# 105358-3SC002-01-A_CPU.net
KiCad netlist of a schematic drawn in Altium Designer
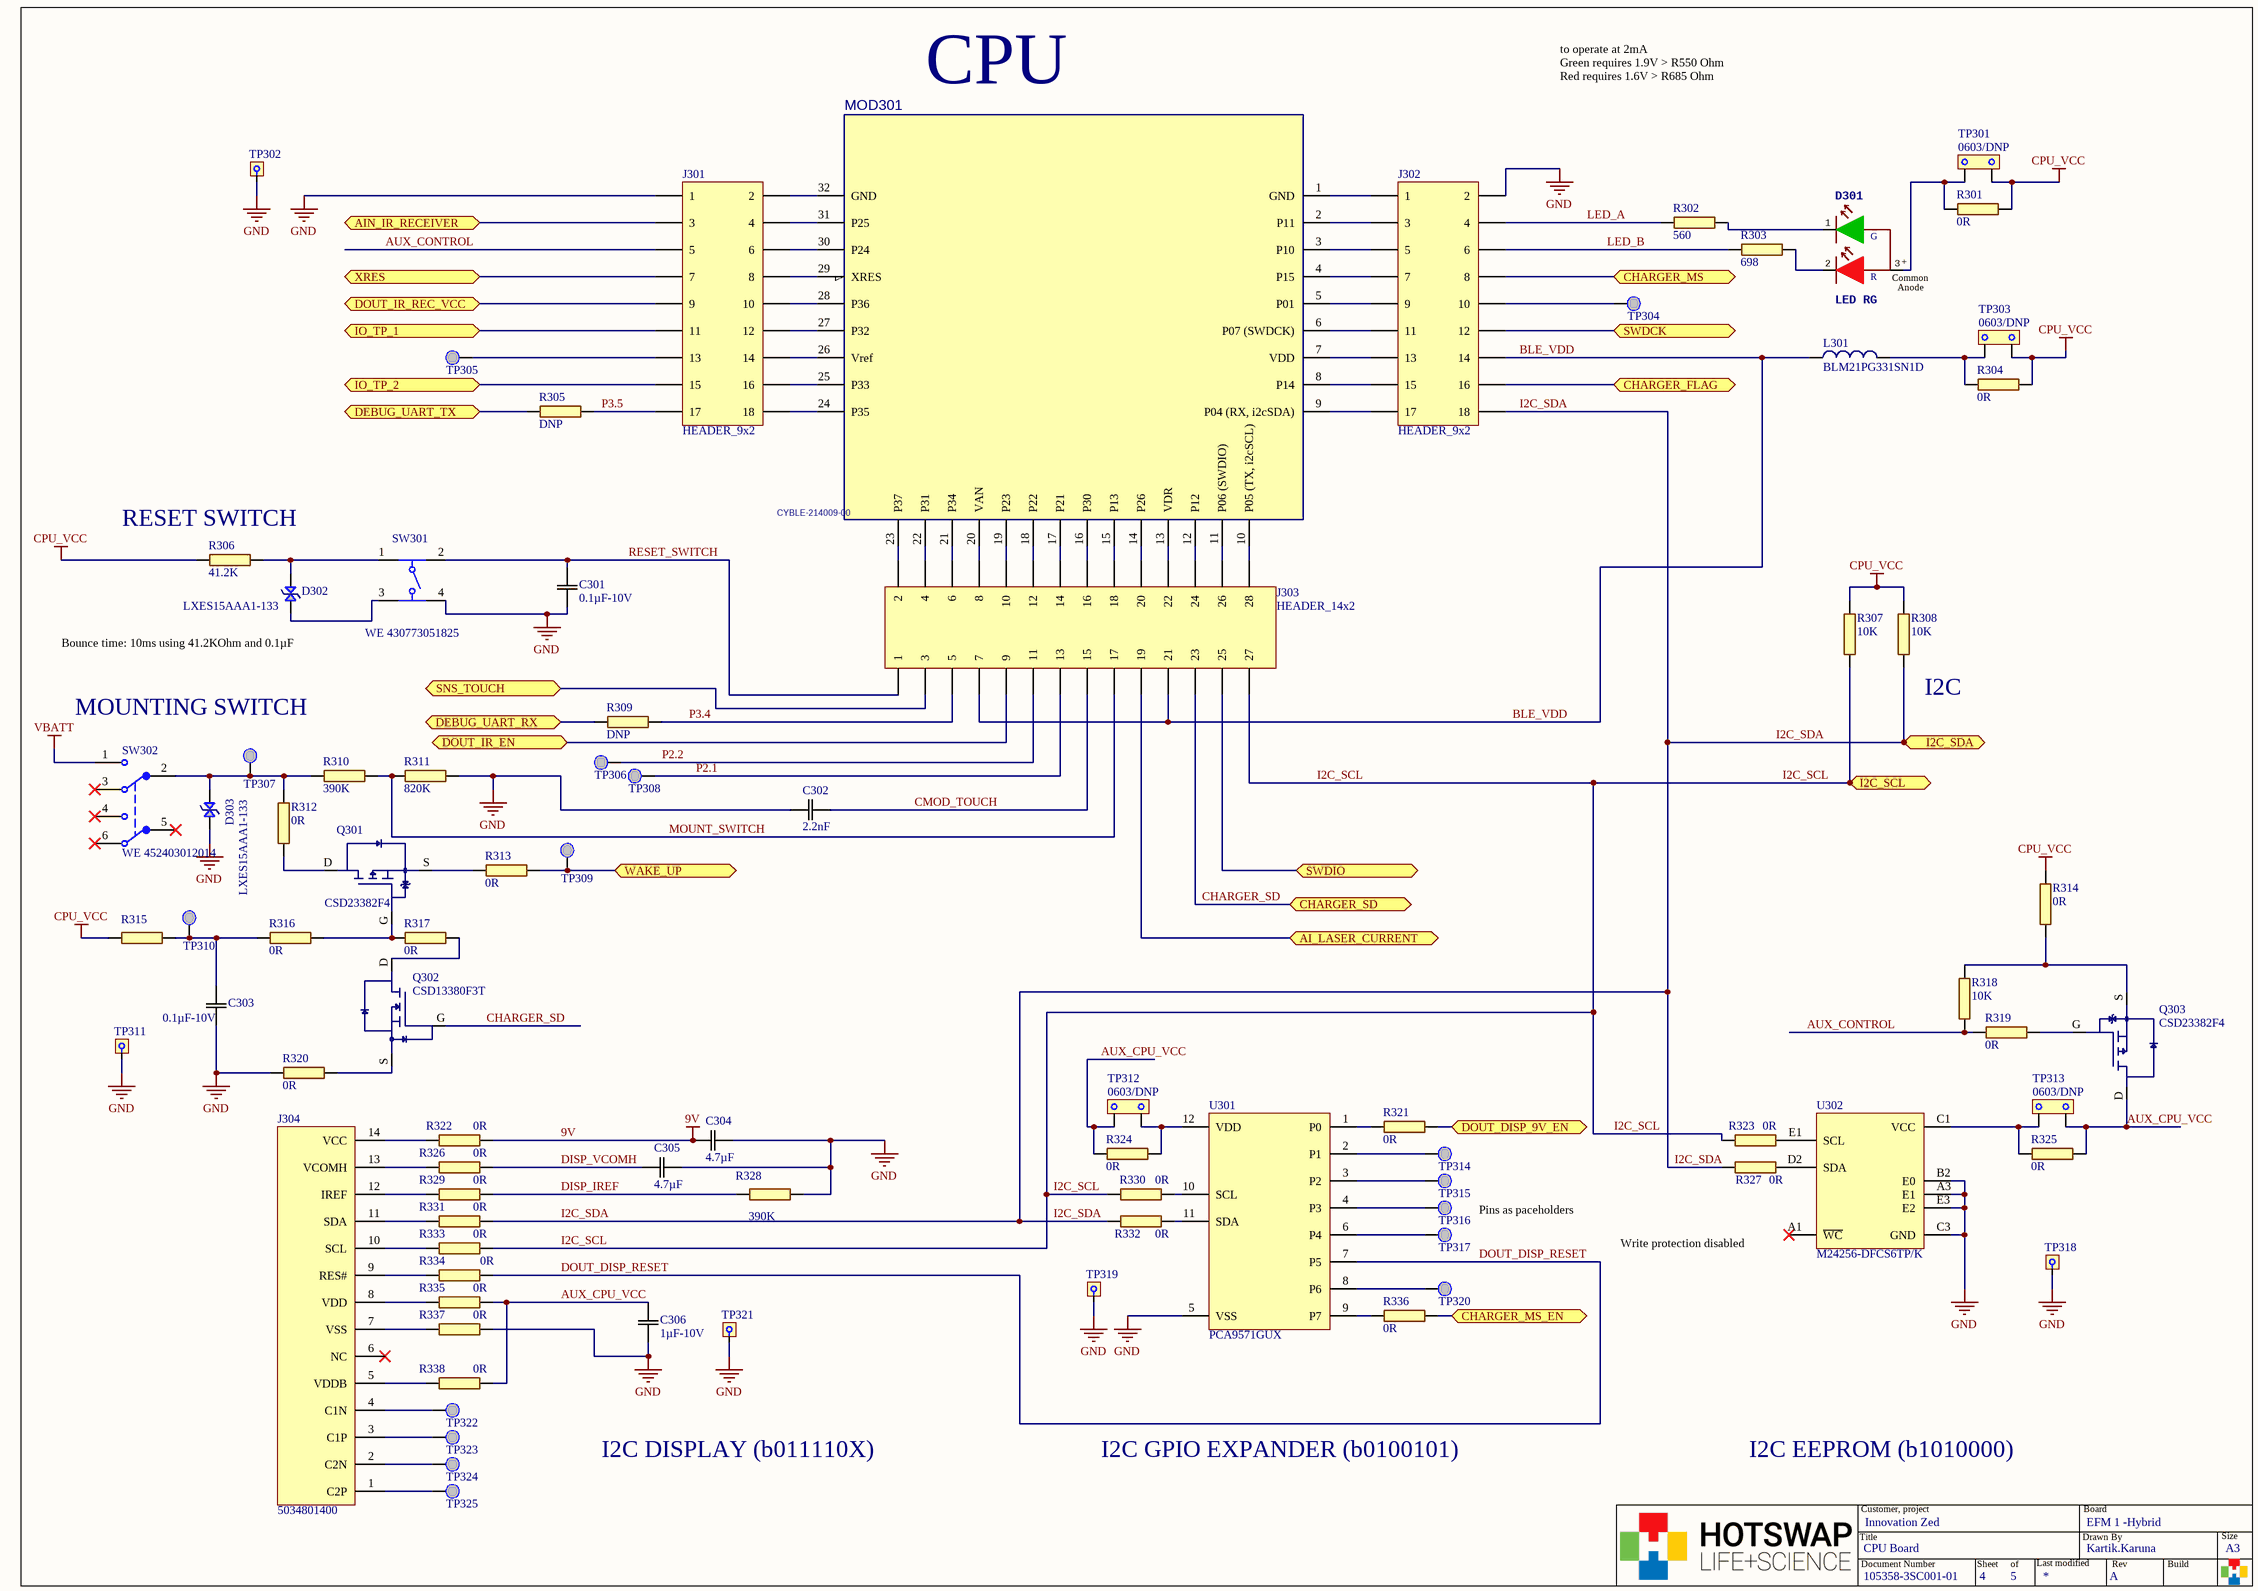
[diagram p0: 105358-3SC002-01-A_CPU.SchDoc]

(export (version "E")
  (design (tool "Eeschema 10.0.6"))
  (components
    (comp (ref "C301")
      (value "0.1µF-10V")
      (footprint "0402C_HIGH_DENSITY")
      (description "0.1µF ±10% 10V X5R Ceramic Capacitor 0402")
      (fields
        (field (name "MANUFACTURER PART NUMBER") "CC0402KRX5R6BB104")
        (field (name "MANUFACTURER") "Yageo")
      )
      (libsource (lib "ConnectMedical") (part "0402C-0.1uF-10V"))
    )
    (comp (ref "C302")
      (value "2.2nF")
      (footprint "0402C_HIGH_DENSITY")
      (description "2.2nF ±10% 50V X5R Ceramic Capacitor 0402")
      (fields
        (field (name "MANUFACTURER PART NUMBER") "GRM155R61H222KA01D")
        (field (name "MANUFACTURER") "Murata Electronics North America")
      )
      (libsource (lib "ConnectMedical") (part "0402C-2.2nF-50V"))
    )
    (comp (ref "C303")
      (value "0.1µF-10V")
      (footprint "0402C_HIGH_DENSITY")
      (description "0.1µF ±10% 10V X5R Ceramic Capacitor 0402")
      (fields
        (field (name "MANUFACTURER PART NUMBER") "CC0402KRX5R6BB104")
        (field (name "MANUFACTURER") "Yageo")
      )
      (libsource (lib "ConnectMedical") (part "0402C-0.1uF-10V"))
    )
    (comp (ref "C304")
      (value "4.7µF")
      (footprint "0402C_HIGH_DENSITY")
      (description "4.7µF ±10% 6.3V X5R Ceramic Capacitor 0402")
      (fields
        (field (name "MANUFACTURER PART NUMBER") "C1005X5R0J475K050BC")
        (field (name "MANUFACTURER") "TDK Corporation")
      )
      (libsource (lib "ConnectMedical") (part "0402C-4.7uF-6.3V"))
    )
    (comp (ref "C305")
      (value "4.7µF")
      (footprint "0402C_HIGH_DENSITY")
      (description "4.7µF ±10% 6.3V X5R Ceramic Capacitor 0402")
      (fields
        (field (name "MANUFACTURER PART NUMBER") "C1005X5R0J475K050BC")
        (field (name "MANUFACTURER") "TDK Corporation")
      )
      (libsource (lib "ConnectMedical") (part "0402C-4.7uF-6.3V"))
    )
    (comp (ref "C306")
      (value "1µF-10V")
      (footprint "0402C_HIGH_DENSITY")
      (description "1µF ±10% 10V X5R Ceramic Capacitor 0402")
      (fields
        (field (name "MANUFACTURER PART NUMBER") "CC0402KRX5R6BB105")
        (field (name "MANUFACTURER") "Yageo")
      )
      (libsource (lib "ConnectMedical") (part "0402C-1uF-10V"))
    )
    (comp (ref "D301")
      (value "LED RG")
      (footprint "LED GRN/RED DIFF 1208 R/A SMD")
      (description "LED GRN/RED DIFF 1208 R/A SMD")
      (fields
        (field (name "MANUFACTURER") "Stanley Electric Co")
        (field (name "MANUFACTURER PART NUMBER") "BRPY1211F-TR")
      )
      (libsource (lib "ConnectMedical") (part "LED GRN/RED DIFF 1208 R/A SMD"))
    )
    (comp (ref "D302")
      (value "LXES15AAA1-133")
      (footprint "0402C-GENERIC")
      (description "TVS DIODE 15VWM 0402")
      (fields
        (field (name "MANUFACTURER") "Murata Electronics North America")
        (field (name "DIGI-KEY PART NUMBER") "490-13209-1-ND")
      )
      (libsource (lib "ConnectMedical") (part "TVS DIODE 15VWM 0402"))
    )
    (comp (ref "D303")
      (value "LXES15AAA1-133")
      (footprint "0402C-GENERIC")
      (description "TVS DIODE 15VWM 0402")
      (fields
        (field (name "MANUFACTURER") "Murata Electronics North America")
        (field (name "DIGI-KEY PART NUMBER") "490-13209-1-ND")
      )
      (libsource (lib "ConnectMedical") (part "TVS DIODE 15VWM 0402"))
    )
    (comp (ref "J301")
      (value "HEADER_9x2")
      (footprint "Pin Header 9 x 2 - 2.54mm")
      (description "18 Positions Header Connector 0.100\" (2.54mm) Through Hole Gold or Gold")
      (fields
        (field (name "MANUFACTURER PART NUMBER") "77313-818-18LF")
        (field (name "MANUFACTURER") "Amphenol FCI")
      )
      (libsource (lib "ConnectMedical") (part "HEADER_9x2"))
    )
    (comp (ref "J302")
      (value "HEADER_9x2")
      (footprint "Pin Header 9 x 2 - 2.54mm")
      (description "18 Positions Header Connector 0.100\" (2.54mm) Through Hole Gold or Gold")
      (fields
        (field (name "MANUFACTURER PART NUMBER") "77313-818-18LF")
        (field (name "MANUFACTURER") "Amphenol FCI")
      )
      (libsource (lib "ConnectMedical") (part "HEADER_9x2"))
    )
    (comp (ref "J303")
      (value "HEADER_14x2")
      (footprint "Pin Header 14 x 2 - 2.54mm")
      (description "CONN HEADER VERT DUAL 28POS 2.54")
      (fields
        (field (name "MANUFACTURER PART NUMBER") "61302821121")
        (field (name "MANUFACTURER") "Wurth Electronics Inc.")
      )
      (libsource (lib "ConnectMedical") (part "HEADER_14x2"))
    )
    (comp (ref "J304")
      (value "5034801400")
      (footprint "5034801400")
      (description "Connector molex to OLED Display")
      (fields (field (name "MANUFACTURER") "Molex, LLC") (field (name "DIGI-KEY PART NUMBER") "WM1442CT-ND"))
      (libsource (lib "ConnectMedical") (part "Molex-5034801400"))
    )
    (comp (ref "L301")
      (value "BLM21PG331SN1D")
      (footprint "0805L_HIGH_DENSITY - Hybrid 0402")
      (description "0805 Ferrite Bead 330Ohm@100MHz")
      (fields
        (field (name "DIGI-KEY PART NUMBER") "490-5988-1-ND")
        (field (name "MANUFACTURER") "Murata Electronics North America")
      )
      (libsource (lib "ConnectMedical") (part "BLM21PG331SN1D"))
    )
    (comp (ref "MOD301")
      (value "CYBLE-214009-00")
      (footprint "CYBLE-014008-00_MinKeepOut")
      (description "BLE PSoC Module 4.1")
      (fields
        (field (name "MANUFACTURER") "Cypress Semiconductor Corp")
        (field (name "DIGI-KEY PART NUMBER") "428-3809-ND")
      )
      (libsource (lib "ConnectMedical") (part "CYBLE-214009-00"))
    )
    (comp (ref "Q301")
      (value "CSD23382F4")
      (footprint "CSD23382F4 -DFN65P100X35-3L")
      (description "MOSFET P-CH 12V 22A 3PICOSTAR")
      (fields
        (field (name "DIGI-KEY PART NUMBER") "296-40003-1-ND")
        (field (name "MANUFACTURER") "Texas Instruments")
      )
      (libsource (lib "ConnectMedical") (part "CSD23382F4"))
    )
    (comp (ref "Q302")
      (value "CSD13380F3T")
      (footprint "CSD13380F3-DFN40P69X35-3L")
      (description "12V N-CHANNEL FEMTOFET MOSFET")
      (fields (field (name "MANUFACTURER") "Texas Instruments"))
      (libsource (lib "ConnectMedical") (part "CSD13380F3T"))
    )
    (comp (ref "Q303")
      (value "CSD23382F4")
      (footprint "CSD23382F4 -DFN65P100X35-3L")
      (description "MOSFET P-CH 12V 22A 3PICOSTAR")
      (fields
        (field (name "DIGI-KEY PART NUMBER") "296-40003-1-ND")
        (field (name "MANUFACTURER") "Texas Instruments")
      )
      (libsource (lib "ConnectMedical") (part "CSD23382F4"))
    )
    (comp (ref "R301")
      (value "0R")
      (footprint "0603R-GENRIC")
      (description "RES SMD 0 OHM 1% 1/10W 0603")
      (fields (field (name "POWER") "0.063W"))
      (libsource (lib "ConnectMedical") (part "0603R-0R -1%-0.063W"))
    )
    (comp (ref "R302")
      (value "560")
      (footprint "0402R-GENERIC")
      (description "RES SMD 560OHM 1% 1/16W 0402")
      (fields
        (field (name "DIGI-KEY PART NUMBER") "1276-3473-1-ND")
        (field (name "MANUFACTURER") "Samsung Electro-Mechanics America, Inc.")
      )
      (libsource (lib "ConnectMedical") (part "0402R-560 OHM-1%-0.063W"))
    )
    (comp (ref "R303")
      (value "698")
      (footprint "0402R-GENERIC")
      (description "RES SMD 698 OHM 1% 1/16W 0402")
      (fields (field (name "DIGI-KEY PART NUMBER") "YAG3215CT-ND") (field (name "MANUFACTURER") "Yageo"))
      (libsource (lib "ConnectMedical") (part "0402R-698 OHM-1%-0.063W"))
    )
    (comp (ref "R304")
      (value "0R")
      (footprint "0603R-GENRIC")
      (description "RES SMD 0 OHM 1% 1/10W 0603")
      (fields (field (name "POWER") "0.063W"))
      (libsource (lib "ConnectMedical") (part "0603R-0R -1%-0.063W"))
    )
    (comp (ref "R305")
      (value "DNP")
      (footprint "0402R-GENERIC")
      (libsource (lib "ConnectMedical") (part "0402R-Do Not Place"))
    )
    (comp (ref "R306")
      (value "41.2K")
      (footprint "0402R-GENERIC")
      (description "RES SMD 41.2kOHM 1% 1/16W 0402")
      (fields (field (name "DIGI-KEY PART NUMBER") "YAG3155CT-ND") (field (name "MANUFACTURER") "Yageo"))
      (libsource (lib "ConnectMedical") (part "0402R-41.2k OHM-1%-0.063W"))
    )
    (comp (ref "R307")
      (value "10K")
      (footprint "0402R-GENERIC")
      (description "RES SMD 10kOHM 1% 1/16W 0402")
      (fields (field (name "DIGI-KEY PART NUMBER") "311-10.0KLRCT-ND") (field (name "MANUFACTURER") "Yageo"))
      (libsource (lib "ConnectMedical") (part "0402R-10k OHM-1%-0.063W"))
    )
    (comp (ref "R308")
      (value "10K")
      (footprint "0402R-GENERIC")
      (description "RES SMD 10kOHM 1% 1/16W 0402")
      (fields (field (name "DIGI-KEY PART NUMBER") "311-10.0KLRCT-ND") (field (name "MANUFACTURER") "Yageo"))
      (libsource (lib "ConnectMedical") (part "0402R-10k OHM-1%-0.063W"))
    )
    (comp (ref "R309")
      (value "DNP")
      (footprint "0402R-GENERIC")
      (libsource (lib "ConnectMedical") (part "0402R-Do Not Place"))
    )
    (comp (ref "R310")
      (value "390K")
      (footprint "0402R-GENERIC")
      (description "RES SMD 390kOHM 1% 1/16W 0402")
      (fields (field (name "DIGI-KEY PART NUMBER") "YAG3143CT-ND") (field (name "MANUFACTURER") "Yageo"))
      (libsource (lib "ConnectMedical") (part "0402R-390k OHM-1%-0.063W"))
    )
    (comp (ref "R311")
      (value "820K")
      (footprint "0402R-GENERIC")
      (description "RES SMD 820kOHM 1% 1/16W 0402")
      (fields (field (name "DIGI-KEY PART NUMBER") "YAG3240CT-ND") (field (name "MANUFACTURER") "Yageo"))
      (libsource (lib "ConnectMedical") (part "0402R-820k OHM-1%-0.063W"))
    )
    (comp (ref "R312")
      (value "0R")
      (footprint "0603R-GENRIC")
      (description "RES SMD 0 OHM 1% 1/10W 0603")
      (fields (field (name "POWER") "0.063W"))
      (libsource (lib "") (part "0603R-0R -1%-0.063W_3"))
    )
    (comp (ref "R313")
      (value "0R")
      (footprint "0603R-GENRIC")
      (description "RES SMD 0 OHM 1% 1/10W 0603")
      (fields (field (name "POWER") "0.063W"))
      (libsource (lib "ConnectMedical") (part "0603R-0R -1%-0.063W"))
    )
    (comp (ref "R314")
      (value "0R")
      (footprint "0603R-GENRIC")
      (description "RES SMD 0 OHM 1% 1/10W 0603")
      (fields (field (name "POWER") "0.063W"))
      (libsource (lib "") (part "0603R-0R -1%-0.063W_2"))
    )
    (comp (ref "R315")
      (value "~")
      (footprint "0402R-GENERIC")
      (description "RES SMD 390kOHM 1% 1/16W 0402")
      (fields (field (name "DIGI-KEY PART NUMBER") "YAG3143CT-ND") (field (name "MANUFACTURER") "Yageo"))
      (libsource (lib "ConnectMedical") (part "0402R-390k OHM-1%-0.063W"))
    )
    (comp (ref "R316")
      (value "0R")
      (footprint "0603R-GENRIC")
      (description "RES SMD 0 OHM 1% 1/10W 0603")
      (fields (field (name "POWER") "0.063W"))
      (libsource (lib "") (part "0603R-0R -1%-0.063W_1"))
    )
    (comp (ref "R317")
      (value "0R")
      (footprint "0603R-GENRIC")
      (description "RES SMD 0 OHM 1% 1/10W 0603")
      (fields (field (name "POWER") "0.063W"))
      (libsource (lib "") (part "0603R-0R -1%-0.063W_1"))
    )
    (comp (ref "R318")
      (value "10K")
      (footprint "0402R-GENERIC")
      (description "RES SMD 10kOHM 1% 1/16W 0402")
      (fields (field (name "DIGI-KEY PART NUMBER") "311-10.0KLRCT-ND") (field (name "MANUFACTURER") "Yageo"))
      (libsource (lib "ConnectMedical") (part "0402R-10k OHM-1%-0.063W"))
    )
    (comp (ref "R319")
      (value "0R")
      (footprint "0603R-GENRIC")
      (description "RES SMD 0 OHM 1% 1/10W 0603")
      (fields (field (name "POWER") "0.063W"))
      (libsource (lib "ConnectMedical") (part "0603R-0R -1%-0.063W"))
    )
    (comp (ref "R320")
      (value "0R")
      (footprint "0603R-GENRIC")
      (description "RES SMD 0 OHM 1% 1/10W 0603")
      (fields (field (name "POWER") "0.063W"))
      (libsource (lib "") (part "0603R-0R -1%-0.063W_1"))
    )
    (comp (ref "R321")
      (value "0R")
      (footprint "0603R-GENRIC")
      (description "RES SMD 0 OHM 1% 1/10W 0603")
      (fields (field (name "POWER") "0.063W"))
      (libsource (lib "ConnectMedical") (part "0603R-0R -1%-0.063W"))
    )
    (comp (ref "R322")
      (value "0R")
      (footprint "0603R-GENRIC")
      (description "RES SMD 0 OHM 1% 1/10W 0603")
      (fields (field (name "POWER") "0.063W"))
      (libsource (lib "ConnectMedical") (part "0603R-0R -1%-0.063W"))
    )
    (comp (ref "R323")
      (value "0R")
      (footprint "0603R-GENRIC")
      (description "RES SMD 0 OHM 1% 1/10W 0603")
      (fields (field (name "POWER") "0.063W"))
      (libsource (lib "ConnectMedical") (part "0603R-0R -1%-0.063W"))
    )
    (comp (ref "R324")
      (value "0R")
      (footprint "0603R-GENRIC")
      (description "RES SMD 0 OHM 1% 1/10W 0603")
      (fields (field (name "POWER") "0.063W"))
      (libsource (lib "ConnectMedical") (part "0603R-0R -1%-0.063W"))
    )
    (comp (ref "R325")
      (value "0R")
      (footprint "0603R-GENRIC")
      (description "RES SMD 0 OHM 1% 1/10W 0603")
      (fields (field (name "POWER") "0.063W"))
      (libsource (lib "ConnectMedical") (part "0603R-0R -1%-0.063W"))
    )
    (comp (ref "R326")
      (value "0R")
      (footprint "0603R-GENRIC")
      (description "RES SMD 0 OHM 1% 1/10W 0603")
      (fields (field (name "POWER") "0.063W"))
      (libsource (lib "ConnectMedical") (part "0603R-0R -1%-0.063W"))
    )
    (comp (ref "R327")
      (value "0R")
      (footprint "0603R-GENRIC")
      (description "RES SMD 0 OHM 1% 1/10W 0603")
      (fields (field (name "POWER") "0.063W"))
      (libsource (lib "ConnectMedical") (part "0603R-0R -1%-0.063W"))
    )
    (comp (ref "R328")
      (value "390K")
      (footprint "0402R-GENERIC")
      (description "RES SMD 390kOHM 1% 1/16W 0402")
      (fields (field (name "DIGI-KEY PART NUMBER") "YAG3143CT-ND") (field (name "MANUFACTURER") "Yageo"))
      (libsource (lib "ConnectMedical") (part "0402R-390k OHM-1%-0.063W"))
    )
    (comp (ref "R329")
      (value "0R")
      (footprint "0603R-GENRIC")
      (description "RES SMD 0 OHM 1% 1/10W 0603")
      (fields (field (name "POWER") "0.063W"))
      (libsource (lib "ConnectMedical") (part "0603R-0R -1%-0.063W"))
    )
    (comp (ref "R330")
      (value "0R")
      (footprint "0603R-GENRIC")
      (description "RES SMD 0 OHM 1% 1/10W 0603")
      (fields (field (name "POWER") "0.063W"))
      (libsource (lib "ConnectMedical") (part "0603R-0R -1%-0.063W"))
    )
    (comp (ref "R331")
      (value "0R")
      (footprint "0603R-GENRIC")
      (description "RES SMD 0 OHM 1% 1/10W 0603")
      (fields (field (name "POWER") "0.063W"))
      (libsource (lib "ConnectMedical") (part "0603R-0R -1%-0.063W"))
    )
    (comp (ref "R332")
      (value "0R")
      (footprint "0603R-GENRIC")
      (description "RES SMD 0 OHM 1% 1/10W 0603")
      (fields (field (name "POWER") "0.063W"))
      (libsource (lib "ConnectMedical") (part "0603R-0R -1%-0.063W"))
    )
    (comp (ref "R333")
      (value "0R")
      (footprint "0603R-GENRIC")
      (description "RES SMD 0 OHM 1% 1/10W 0603")
      (fields (field (name "POWER") "0.063W"))
      (libsource (lib "ConnectMedical") (part "0603R-0R -1%-0.063W"))
    )
    (comp (ref "R334")
      (value "0R")
      (footprint "0603R-GENRIC")
      (description "RES SMD 0 OHM 1% 1/10W 0603")
      (fields (field (name "POWER") "0.063W"))
      (libsource (lib "ConnectMedical") (part "0603R-0R -1%-0.063W"))
    )
    (comp (ref "R335")
      (value "0R")
      (footprint "0603R-GENRIC")
      (description "RES SMD 0 OHM 1% 1/10W 0603")
      (fields (field (name "POWER") "0.063W"))
      (libsource (lib "ConnectMedical") (part "0603R-0R -1%-0.063W"))
    )
    (comp (ref "R336")
      (value "0R")
      (footprint "0603R-GENRIC")
      (description "RES SMD 0 OHM 1% 1/10W 0603")
      (fields (field (name "POWER") "0.063W"))
      (libsource (lib "ConnectMedical") (part "0603R-0R -1%-0.063W"))
    )
    (comp (ref "R337")
      (value "0R")
      (footprint "0603R-GENRIC")
      (description "RES SMD 0 OHM 1% 1/10W 0603")
      (fields (field (name "POWER") "0.063W"))
      (libsource (lib "ConnectMedical") (part "0603R-0R -1%-0.063W"))
    )
    (comp (ref "R338")
      (value "0R")
      (footprint "0603R-GENRIC")
      (description "RES SMD 0 OHM 1% 1/10W 0603")
      (fields (field (name "POWER") "0.063W"))
      (libsource (lib "ConnectMedical") (part "0603R-0R -1%-0.063W"))
    )
    (comp (ref "SW301")
      (value "WE 430773051825")
      (footprint "4307x30518xx_6x6x5.1")
      (description "WS-TASV 6x6mm J-Hook Hermetic Tact Switch, SMD version")
      (fields
        (field (name "MANUFACTURER PART NUMBER") "430773051825")
        (field (name "MANUFACTURER") "Wurth Elektronik")
      )
      (libsource (lib "ConnectMedical") (part "WE_430773051825"))
    )
    (comp (ref "SW302")
      (value "WE 452403012014")
      (footprint "WE452403012014")
      (description "WS-SLSV 7.65x5.5 mm SMD Vertical")
      (fields (field (name "PART NUMBER") "452403012014") (field (name "PUBLISHER") "Wurth Elektronik"))
      (libsource (lib "ConnectMedical") (part "SWITCH-TOGGLE_452403012014"))
    )
    (comp (ref "TP301")
      (value "0603/DNP")
      (footprint "TESTPOINT_C_R0608")
      (description "Test point for Med Current 0402 JUMPER SMD O OHM 1% 1/4W 0603")
      (libsource (lib "ConnectMedical") (part "TP_C_R0603"))
    )
    (comp (ref "TP302")
      (value "TP_V_HOOK")
      (footprint "Testpoint_Hook")
      (description "Black PC Test Point")
      (fields
        (field (name "DIGI-KEY PART NUMBER") "36-5001-ND")
        (field (name "MANUFACTURER") "Keystone Electronics")
      )
      (libsource (lib "ConnectMedical") (part "TP_V_HOOK"))
    )
    (comp (ref "TP303")
      (value "0603/DNP")
      (footprint "TESTPOINT_C_R0608")
      (description "Test point for Med Current 0402 JUMPER SMD O OHM 1% 1/4W 0603")
      (libsource (lib "ConnectMedical") (part "TP_C_R0603"))
    )
    (comp (ref "TP304")
      (value "TEST POINT")
      (footprint "PAD TEST POINT")
      (description "Testing Poiny")
      (libsource (lib "ConnectMedical") (part "TEST POINT"))
    )
    (comp (ref "TP305")
      (value "TEST POINT")
      (footprint "PAD TEST POINT")
      (description "Testing Poiny")
      (libsource (lib "ConnectMedical") (part "TEST POINT"))
    )
    (comp (ref "TP306")
      (value "TEST POINT")
      (footprint "PAD TEST POINT")
      (description "Testing Poiny")
      (libsource (lib "ConnectMedical") (part "TEST POINT"))
    )
    (comp (ref "TP307")
      (value "TEST POINT")
      (footprint "PAD TEST POINT")
      (description "Testing Poiny")
      (libsource (lib "ConnectMedical") (part "TEST POINT"))
    )
    (comp (ref "TP308")
      (value "TEST POINT")
      (footprint "PAD TEST POINT")
      (description "Testing Poiny")
      (libsource (lib "ConnectMedical") (part "TEST POINT"))
    )
    (comp (ref "TP309")
      (value "TEST POINT")
      (footprint "PAD TEST POINT")
      (description "Testing Poiny")
      (libsource (lib "ConnectMedical") (part "TEST POINT"))
    )
    (comp (ref "TP310")
      (value "TEST POINT")
      (footprint "PAD TEST POINT")
      (description "Testing Poiny")
      (libsource (lib "ConnectMedical") (part "TEST POINT"))
    )
    (comp (ref "TP311")
      (value "TP_V_HOOK")
      (footprint "Testpoint_Hook")
      (description "Black PC Test Point")
      (fields
        (field (name "DIGI-KEY PART NUMBER") "36-5001-ND")
        (field (name "MANUFACTURER") "Keystone Electronics")
      )
      (libsource (lib "ConnectMedical") (part "TP_V_HOOK"))
    )
    (comp (ref "TP312")
      (value "0603/DNP")
      (footprint "TESTPOINT_C_R0608")
      (description "Test point for Med Current 0402 JUMPER SMD O OHM 1% 1/4W 0603")
      (libsource (lib "ConnectMedical") (part "TP_C_R0603"))
    )
    (comp (ref "TP313")
      (value "0603/DNP")
      (footprint "TESTPOINT_C_R0608")
      (description "Test point for Med Current 0402 JUMPER SMD O OHM 1% 1/4W 0603")
      (libsource (lib "ConnectMedical") (part "TP_C_R0603"))
    )
    (comp (ref "TP314")
      (value "TEST POINT")
      (footprint "PAD TEST POINT")
      (description "Testing Poiny")
      (libsource (lib "ConnectMedical") (part "TEST POINT"))
    )
    (comp (ref "TP315")
      (value "TEST POINT")
      (footprint "PAD TEST POINT")
      (description "Testing Poiny")
      (libsource (lib "ConnectMedical") (part "TEST POINT"))
    )
    (comp (ref "TP316")
      (value "TEST POINT")
      (footprint "PAD TEST POINT")
      (description "Testing Poiny")
      (libsource (lib "ConnectMedical") (part "TEST POINT"))
    )
    (comp (ref "TP317")
      (value "TEST POINT")
      (footprint "PAD TEST POINT")
      (description "Testing Poiny")
      (libsource (lib "ConnectMedical") (part "TEST POINT"))
    )
    (comp (ref "TP318")
      (value "TP_V_HOOK")
      (footprint "Testpoint_Hook")
      (description "Black PC Test Point")
      (fields
        (field (name "DIGI-KEY PART NUMBER") "36-5001-ND")
        (field (name "MANUFACTURER") "Keystone Electronics")
      )
      (libsource (lib "ConnectMedical") (part "TP_V_HOOK"))
    )
    (comp (ref "TP319")
      (value "TP_V_HOOK")
      (footprint "Testpoint_Hook")
      (description "Black PC Test Point")
      (fields
        (field (name "DIGI-KEY PART NUMBER") "36-5001-ND")
        (field (name "MANUFACTURER") "Keystone Electronics")
      )
      (libsource (lib "ConnectMedical") (part "TP_V_HOOK"))
    )
    (comp (ref "TP320")
      (value "TEST POINT")
      (footprint "PAD TEST POINT")
      (description "Testing Poiny")
      (libsource (lib "ConnectMedical") (part "TEST POINT"))
    )
    (comp (ref "TP321")
      (value "TP_V_HOOK")
      (footprint "Testpoint_Hook")
      (description "Black PC Test Point")
      (fields
        (field (name "DIGI-KEY PART NUMBER") "36-5001-ND")
        (field (name "MANUFACTURER") "Keystone Electronics")
      )
      (libsource (lib "ConnectMedical") (part "TP_V_HOOK"))
    )
    (comp (ref "TP322")
      (value "TEST POINT")
      (footprint "PAD TEST POINT")
      (description "Testing Poiny")
      (libsource (lib "ConnectMedical") (part "TEST POINT"))
    )
    (comp (ref "TP323")
      (value "TEST POINT")
      (footprint "PAD TEST POINT")
      (description "Testing Poiny")
      (libsource (lib "ConnectMedical") (part "TEST POINT"))
    )
    (comp (ref "TP324")
      (value "TEST POINT")
      (footprint "PAD TEST POINT")
      (description "Testing Poiny")
      (libsource (lib "ConnectMedical") (part "TEST POINT"))
    )
    (comp (ref "TP325")
      (value "TEST POINT")
      (footprint "PAD TEST POINT")
      (description "Testing Poiny")
      (libsource (lib "ConnectMedical") (part "TEST POINT"))
    )
    (comp (ref "U301")
      (value "PCA9571GUX")
      (footprint "PCA9571-XQFN12")
      (description "IC I/O EXPANDER I2C 12XQFN")
      (fields
        (field (name "MANUFACTURER") "NXP USA Inc.")
        (field (name "DIGI-KEY PART NUMBER") "568-12400-1-ND")
      )
      (libsource (lib "ConnectMedical") (part "PCA9571GUX"))
    )
    (comp (ref "U302")
      (value "M24256-DFCS6TP/K")
      (footprint "BGAS8_M24256-DFCS6_1")
      (description "IC EEPROM 256KBIT 1MHZ 8WLCSP")
      (fields
        (field (name "MANUFACTURER") "STMicroelectronics")
        (field (name "DIGI-KEY PART NUMBER") "497-13611-1-ND")
      )
      (libsource (lib "ConnectMedical") (part "M24256-DFCS6TPK"))
    )
  )
  (nets
    (net (code "1") (name "/AIN_IR_RECEIVER") (class "Default")
      (node (ref "J301") (pin "3") (pinfunction "3_3") (pintype "passive"))
    )
    (net (code "2") (name "/AI_LASER_CURRENT") (class "Default")
      (node (ref "J303") (pin "19") (pinfunction "19_19") (pintype "passive"))
    )
    (net (code "3") (name "/AUX_CONTROL") (class "Default")
      (node (ref "J301") (pin "5") (pinfunction "5_5") (pintype "passive"))
      (node (ref "R318") (pin "2") (pintype "passive"))
      (node (ref "R319") (pin "1") (pintype "passive"))
    )
    (net (code "4") (name "/AUX_CPU_VCC") (class "Default")
      (node (ref "C306") (pin "2") (pinfunction "2_2") (pintype "passive"))
      (node (ref "Q303") (pin "D") (pinfunction "3_D") (pintype "passive"))
      (node (ref "R324") (pin "1") (pintype "passive"))
      (node (ref "R325") (pin "2") (pintype "passive"))
      (node (ref "R335") (pin "2") (pintype "passive"))
      (node (ref "R338") (pin "2") (pintype "passive"))
      (node (ref "TP312") (pin "1") (pintype "power_in"))
      (node (ref "TP313") (pin "2") (pintype "power_in"))
    )
    (net (code "5") (name "/BLE_VDD") (class "Default")
      (node (ref "J302") (pin "14") (pinfunction "14_14") (pintype "passive"))
      (node (ref "J303") (pin "21") (pinfunction "21_21") (pintype "passive"))
      (node (ref "J303") (pin "7") (pinfunction "7_7") (pintype "passive"))
      (node (ref "L301") (pin "1") (pinfunction "1_1") (pintype "passive"))
    )
    (net (code "6") (name "/CHARGER_FLAG") (class "Default")
      (node (ref "J302") (pin "16") (pinfunction "16_16") (pintype "passive"))
    )
    (net (code "7") (name "/CHARGER_MS") (class "Default")
      (node (ref "J302") (pin "8") (pinfunction "8_8") (pintype "passive"))
    )
    (net (code "8") (name "/CHARGER_MS_EN") (class "Default")
      (node (ref "R336") (pin "2") (pintype "passive"))
    )
    (net (code "9") (name "/CHARGER_SD") (class "Default")
      (node (ref "J303") (pin "23") (pinfunction "23_23") (pintype "passive"))
      (node (ref "Q302") (pin "G") (pinfunction "1_G") (pintype "passive"))
    )
    (net (code "10") (name "/CMOD_TOUCH") (class "Default")
      (node (ref "C302") (pin "1") (pinfunction "1_1") (pintype "passive"))
      (node (ref "J303") (pin "15") (pinfunction "15_15") (pintype "passive"))
    )
    (net (code "11") (name "/DEBUG_UART_RX") (class "Default")
      (node (ref "R309") (pin "1") (pintype "passive"))
    )
    (net (code "12") (name "/DEBUG_UART_TX") (class "Default")
      (node (ref "R305") (pin "1") (pintype "passive"))
    )
    (net (code "13") (name "/DISP_IREF") (class "Default")
      (node (ref "R328") (pin "1") (pintype "passive"))
      (node (ref "R329") (pin "2") (pintype "passive"))
    )
    (net (code "14") (name "/DISP_VCOMH") (class "Default")
      (node (ref "C305") (pin "2") (pinfunction "2_2") (pintype "passive"))
      (node (ref "R326") (pin "2") (pintype "passive"))
    )
    (net (code "15") (name "/DOUT_DISP_9V_EN") (class "Default")
      (node (ref "R321") (pin "2") (pintype "passive"))
    )
    (net (code "16") (name "/DOUT_DISP_RESET") (class "Default")
      (node (ref "R334") (pin "2") (pintype "passive"))
      (node (ref "U301") (pin "7") (pinfunction "P5_7") (pintype "passive"))
    )
    (net (code "17") (name "/DOUT_IR_EN") (class "Default")
      (node (ref "J303") (pin "9") (pinfunction "9_9") (pintype "passive"))
    )
    (net (code "18") (name "/DOUT_IR_REC_VCC") (class "Default")
      (node (ref "J301") (pin "9") (pinfunction "9_9") (pintype "passive"))
    )
    (net (code "19") (name "/I2C_SCL") (class "Default")
      (node (ref "J303") (pin "27") (pinfunction "27_27") (pintype "passive"))
      (node (ref "R307") (pin "2") (pintype "passive"))
      (node (ref "R323") (pin "1") (pintype "passive"))
      (node (ref "R330") (pin "1") (pintype "passive"))
      (node (ref "R333") (pin "2") (pintype "passive"))
    )
    (net (code "20") (name "/I2C_SDA") (class "Default")
      (node (ref "J302") (pin "18") (pinfunction "18_18") (pintype "passive"))
      (node (ref "R308") (pin "2") (pintype "passive"))
      (node (ref "R327") (pin "1") (pintype "passive"))
      (node (ref "R331") (pin "2") (pintype "passive"))
      (node (ref "R332") (pin "1") (pintype "passive"))
    )
    (net (code "21") (name "/IO_TP_1") (class "Default")
      (node (ref "J301") (pin "11") (pinfunction "11_11") (pintype "passive"))
    )
    (net (code "22") (name "/IO_TP_2") (class "Default")
      (node (ref "J301") (pin "15") (pinfunction "15_15") (pintype "passive"))
    )
    (net (code "23") (name "/LED_A") (class "Default")
      (node (ref "J302") (pin "4") (pinfunction "4_4") (pintype "passive"))
      (node (ref "R302") (pin "1") (pintype "passive"))
    )
    (net (code "24") (name "/LED_B") (class "Default")
      (node (ref "J302") (pin "6") (pinfunction "6_6") (pintype "passive"))
      (node (ref "R303") (pin "1") (pintype "passive"))
    )
    (net (code "25") (name "/MOUNT_SWITCH") (class "Default")
      (node (ref "J303") (pin "17") (pinfunction "17_17") (pintype "passive"))
      (node (ref "R310") (pin "2") (pintype "passive"))
      (node (ref "R311") (pin "2") (pintype "passive"))
    )
    (net (code "26") (name "/P2.1") (class "Default")
      (node (ref "J303") (pin "13") (pinfunction "13_13") (pintype "passive"))
      (node (ref "TP308") (pin "1") (pinfunction "Test_Point_1") (pintype "passive"))
    )
    (net (code "27") (name "/P2.2") (class "Default")
      (node (ref "J303") (pin "11") (pinfunction "11_11") (pintype "passive"))
      (node (ref "TP306") (pin "1") (pinfunction "Test_Point_1") (pintype "passive"))
    )
    (net (code "28") (name "/P3.4") (class "Default")
      (node (ref "J303") (pin "5") (pinfunction "5_5") (pintype "passive"))
      (node (ref "R309") (pin "2") (pintype "passive"))
    )
    (net (code "29") (name "/P3.5") (class "Default")
      (node (ref "J301") (pin "17") (pinfunction "17_17") (pintype "passive"))
      (node (ref "R305") (pin "2") (pintype "passive"))
    )
    (net (code "30") (name "/RESET_SWITCH") (class "Default")
      (node (ref "C301") (pin "2") (pinfunction "2_2") (pintype "passive"))
      (node (ref "J303") (pin "1") (pinfunction "1_1") (pintype "passive"))
      (node (ref "SW301") (pin "2") (pinfunction "2_2") (pintype "passive"))
    )
    (net (code "31") (name "/SNS_TOUCH") (class "Default")
      (node (ref "J303") (pin "3") (pinfunction "3_3") (pintype "passive"))
    )
    (net (code "32") (name "/SWDCK") (class "Default")
      (node (ref "J302") (pin "12") (pinfunction "12_12") (pintype "passive"))
    )
    (net (code "33") (name "/SWDIO") (class "Default")
      (node (ref "J303") (pin "25") (pinfunction "25_25") (pintype "passive"))
    )
    (net (code "34") (name "/WAKE_UP") (class "Default")
      (node (ref "R313") (pin "2") (pintype "passive"))
      (node (ref "TP309") (pin "1") (pinfunction "Test_Point_1") (pintype "passive"))
    )
    (net (code "35") (name "/XRES") (class "Default")
      (node (ref "J301") (pin "7") (pinfunction "7_7") (pintype "passive"))
    )
    (net (code "36") (name "9V") (class "Default")
      (node (ref "C304") (pin "1") (pinfunction "1_1") (pintype "passive"))
      (node (ref "R322") (pin "2") (pintype "passive"))
    )
    (net (code "37") (name "CPU_VCC") (class "Default")
      (node (ref "R301") (pin "2") (pintype "passive"))
      (node (ref "R304") (pin "2") (pintype "passive"))
      (node (ref "R306") (pin "1") (pintype "passive"))
      (node (ref "R307") (pin "1") (pintype "passive"))
      (node (ref "R308") (pin "1") (pintype "passive"))
      (node (ref "R314") (pin "2") (pintype "passive"))
      (node (ref "R315") (pin "1") (pintype "passive"))
      (node (ref "TP301") (pin "2") (pintype "power_in"))
      (node (ref "TP303") (pin "2") (pintype "power_in"))
    )
    (net (code "38") (name "GND") (class "Default")
      (node (ref "C301") (pin "1") (pinfunction "1_1") (pintype "passive"))
      (node (ref "C302") (pin "2") (pinfunction "2_2") (pintype "passive"))
      (node (ref "C303") (pin "1") (pinfunction "1_1") (pintype "passive"))
      (node (ref "C304") (pin "2") (pinfunction "2_2") (pintype "passive"))
      (node (ref "C305") (pin "1") (pinfunction "1_1") (pintype "passive"))
      (node (ref "C306") (pin "1") (pinfunction "1_1") (pintype "passive"))
      (node (ref "D303") (pin "1") (pinfunction "1_1") (pintype "passive"))
      (node (ref "J301") (pin "1") (pinfunction "1_1") (pintype "passive"))
      (node (ref "J302") (pin "2") (pinfunction "2_2") (pintype "passive"))
      (node (ref "R311") (pin "1") (pintype "passive"))
      (node (ref "R320") (pin "2") (pintype "passive"))
      (node (ref "R328") (pin "2") (pintype "passive"))
      (node (ref "R337") (pin "2") (pintype "passive"))
      (node (ref "SW301") (pin "4") (pinfunction "4_4") (pintype "passive"))
      (node (ref "TP302") (pin "1") (pinfunction "8_1") (pintype "passive"))
      (node (ref "TP311") (pin "1") (pinfunction "8_1") (pintype "passive"))
      (node (ref "TP318") (pin "1") (pinfunction "8_1") (pintype "passive"))
      (node (ref "TP319") (pin "1") (pinfunction "8_1") (pintype "passive"))
      (node (ref "TP321") (pin "1") (pinfunction "8_1") (pintype "passive"))
      (node (ref "U301") (pin "5") (pinfunction "VSS_5") (pintype "passive"))
      (node (ref "U302") (pin "A3") (pinfunction "E1_A3") (pintype "passive"))
      (node (ref "U302") (pin "B2") (pinfunction "E0_B2") (pintype "passive"))
      (node (ref "U302") (pin "C3") (pinfunction "GND_C3") (pintype "passive"))
      (node (ref "U302") (pin "E3") (pinfunction "E2_E3") (pintype "passive"))
    )
    (net (code "39") (name "Net-(D301-G)") (class "Default")
      (node (ref "D301") (pin "2") (pinfunction "G_2") (pintype "passive"))
      (node (ref "R303") (pin "2") (pintype "passive"))
    )
    (net (code "40") (name "Net-(D301-Pad3)") (class "Default")
      (node (ref "D301") (pin "3") (pinfunction "3_3") (pintype "passive"))
      (node (ref "R301") (pin "1") (pintype "passive"))
      (node (ref "TP301") (pin "1") (pintype "power_in"))
    )
    (net (code "41") (name "Net-(D301-R)") (class "Default")
      (node (ref "D301") (pin "1") (pinfunction "R_1") (pintype "passive"))
      (node (ref "R302") (pin "2") (pintype "passive"))
    )
    (net (code "42") (name "Net-(D302-Pad1)") (class "Default")
      (node (ref "D302") (pin "1") (pinfunction "1_1") (pintype "passive"))
      (node (ref "SW301") (pin "3") (pinfunction "3_3") (pintype "passive"))
    )
    (net (code "43") (name "Net-(D302-Pad2)") (class "Default")
      (node (ref "D302") (pin "2") (pinfunction "2_2") (pintype "passive"))
      (node (ref "R306") (pin "2") (pintype "passive"))
      (node (ref "SW301") (pin "1") (pinfunction "1_1") (pintype "passive"))
    )
    (net (code "44") (name "Net-(J301-Pad2)") (class "Default")
      (node (ref "J301") (pin "2") (pinfunction "2_2") (pintype "passive"))
      (node (ref "MOD301") (pin "32") (pinfunction "GND_32") (pintype "power_in"))
    )
    (net (code "45") (name "Net-(J302-Pad1)") (class "Default")
      (node (ref "J302") (pin "1") (pinfunction "1_1") (pintype "passive"))
      (node (ref "MOD301") (pin "1") (pinfunction "GND_1") (pintype "power_in"))
    )
    (net (code "46") (name "Net-(J304-C1N)") (class "Default")
      (node (ref "J304") (pin "4") (pinfunction "C1N_4") (pintype "passive"))
      (node (ref "TP322") (pin "1") (pinfunction "Test_Point_1") (pintype "passive"))
    )
    (net (code "47") (name "Net-(J304-C1P)") (class "Default")
      (node (ref "J304") (pin "3") (pinfunction "C1P_3") (pintype "passive"))
      (node (ref "TP323") (pin "1") (pinfunction "Test_Point_1") (pintype "passive"))
    )
    (net (code "48") (name "Net-(J304-C2N)") (class "Default")
      (node (ref "J304") (pin "2") (pinfunction "C2N_2") (pintype "passive"))
      (node (ref "TP324") (pin "1") (pinfunction "Test_Point_1") (pintype "passive"))
    )
    (net (code "49") (name "Net-(J304-C2P)") (class "Default")
      (node (ref "J304") (pin "1") (pinfunction "C2P_1") (pintype "passive"))
      (node (ref "TP325") (pin "1") (pinfunction "Test_Point_1") (pintype "passive"))
    )
    (net (code "50") (name "Net-(J304-IREF)") (class "Default")
      (node (ref "J304") (pin "12") (pinfunction "IREF_12") (pintype "passive"))
      (node (ref "R329") (pin "1") (pintype "passive"))
    )
    (net (code "51") (name "Net-(J304-RES#)") (class "Default")
      (node (ref "J304") (pin "9") (pinfunction "RES#_9") (pintype "passive"))
      (node (ref "R334") (pin "1") (pintype "passive"))
    )
    (net (code "52") (name "Net-(J304-SCL)") (class "Default")
      (node (ref "J304") (pin "10") (pinfunction "SCL_10") (pintype "passive"))
      (node (ref "R333") (pin "1") (pintype "passive"))
    )
    (net (code "53") (name "Net-(J304-SDA)") (class "Default")
      (node (ref "J304") (pin "11") (pinfunction "SDA_11") (pintype "passive"))
      (node (ref "R331") (pin "1") (pintype "passive"))
    )
    (net (code "54") (name "Net-(J304-VCC)") (class "Default")
      (node (ref "J304") (pin "14") (pinfunction "VCC_14") (pintype "passive"))
      (node (ref "R322") (pin "1") (pintype "passive"))
    )
    (net (code "55") (name "Net-(J304-VCOMH)") (class "Default")
      (node (ref "J304") (pin "13") (pinfunction "VCOMH_13") (pintype "passive"))
      (node (ref "R326") (pin "1") (pintype "passive"))
    )
    (net (code "56") (name "Net-(J304-VDD)") (class "Default")
      (node (ref "J304") (pin "8") (pinfunction "VDD_8") (pintype "passive"))
      (node (ref "R335") (pin "1") (pintype "passive"))
    )
    (net (code "57") (name "Net-(J304-VDDB)") (class "Default")
      (node (ref "J304") (pin "5") (pinfunction "VDDB_5") (pintype "passive"))
      (node (ref "R338") (pin "1") (pintype "passive"))
    )
    (net (code "58") (name "Net-(J304-VSS)") (class "Default")
      (node (ref "J304") (pin "7") (pinfunction "VSS_7") (pintype "power_in"))
      (node (ref "R337") (pin "1") (pintype "passive"))
    )
    (net (code "59") (name "Net-(L301-Pad2)") (class "Default")
      (node (ref "L301") (pin "2") (pinfunction "2_2") (pintype "passive"))
      (node (ref "R304") (pin "1") (pintype "passive"))
      (node (ref "TP303") (pin "1") (pintype "power_in"))
    )
    (net (code "60") (name "Net-(MOD301-P01)") (class "Default")
      (node (ref "J302") (pin "9") (pinfunction "9_9") (pintype "passive"))
      (node (ref "MOD301") (pin "5") (pinfunction "P01_5") (pintype "passive"))
    )
    (net (code "61") (name "Net-(MOD301-P04_(RX,_i2cSDA))") (class "Default")
      (node (ref "J302") (pin "17") (pinfunction "17_17") (pintype "passive"))
      (node (ref "MOD301") (pin "9") (pinfunction "P04_(RX,_i2cSDA)_9") (pintype "passive"))
    )
    (net (code "62") (name "Net-(MOD301-P05_(TX,_i2cSCL))") (class "Default")
      (node (ref "J303") (pin "28") (pinfunction "28_28") (pintype "passive"))
      (node (ref "MOD301") (pin "10") (pinfunction "P05_(TX,_i2cSCL)_10") (pintype "passive"))
    )
    (net (code "63") (name "Net-(MOD301-P06_(SWDIO))") (class "Default")
      (node (ref "J303") (pin "26") (pinfunction "26_26") (pintype "passive"))
      (node (ref "MOD301") (pin "11") (pinfunction "P06_(SWDIO)_11") (pintype "passive"))
    )
    (net (code "64") (name "Net-(MOD301-P07_(SWDCK))") (class "Default")
      (node (ref "J302") (pin "11") (pinfunction "11_11") (pintype "passive"))
      (node (ref "MOD301") (pin "6") (pinfunction "P07_(SWDCK)_6") (pintype "passive"))
    )
    (net (code "65") (name "Net-(MOD301-P10)") (class "Default")
      (node (ref "J302") (pin "5") (pinfunction "5_5") (pintype "passive"))
      (node (ref "MOD301") (pin "3") (pinfunction "P10_3") (pintype "passive"))
    )
    (net (code "66") (name "Net-(MOD301-P11)") (class "Default")
      (node (ref "J302") (pin "3") (pinfunction "3_3") (pintype "passive"))
      (node (ref "MOD301") (pin "2") (pinfunction "P11_2") (pintype "passive"))
    )
    (net (code "67") (name "Net-(MOD301-P12)") (class "Default")
      (node (ref "J303") (pin "24") (pinfunction "24_24") (pintype "passive"))
      (node (ref "MOD301") (pin "12") (pinfunction "P12_12") (pintype "passive"))
    )
    (net (code "68") (name "Net-(MOD301-P13)") (class "Default")
      (node (ref "J303") (pin "18") (pinfunction "18_18") (pintype "passive"))
      (node (ref "MOD301") (pin "15") (pinfunction "P13_15") (pintype "passive"))
    )
    (net (code "69") (name "Net-(MOD301-P14)") (class "Default")
      (node (ref "J302") (pin "15") (pinfunction "15_15") (pintype "passive"))
      (node (ref "MOD301") (pin "8") (pinfunction "P14_8") (pintype "passive"))
    )
    (net (code "70") (name "Net-(MOD301-P15)") (class "Default")
      (node (ref "J302") (pin "7") (pinfunction "7_7") (pintype "passive"))
      (node (ref "MOD301") (pin "4") (pinfunction "P15_4") (pintype "passive"))
    )
    (net (code "71") (name "Net-(MOD301-P21)") (class "Default")
      (node (ref "J303") (pin "14") (pinfunction "14_14") (pintype "passive"))
      (node (ref "MOD301") (pin "17") (pinfunction "P21_17") (pintype "passive"))
    )
    (net (code "72") (name "Net-(MOD301-P22)") (class "Default")
      (node (ref "J303") (pin "12") (pinfunction "12_12") (pintype "passive"))
      (node (ref "MOD301") (pin "18") (pinfunction "P22_18") (pintype "passive"))
    )
    (net (code "73") (name "Net-(MOD301-P23)") (class "Default")
      (node (ref "J303") (pin "10") (pinfunction "10_10") (pintype "passive"))
      (node (ref "MOD301") (pin "19") (pinfunction "P23_19") (pintype "passive"))
    )
    (net (code "74") (name "Net-(MOD301-P24)") (class "Default")
      (node (ref "J301") (pin "6") (pinfunction "6_6") (pintype "passive"))
      (node (ref "MOD301") (pin "30") (pinfunction "P24_30") (pintype "passive"))
    )
    (net (code "75") (name "Net-(MOD301-P25)") (class "Default")
      (node (ref "J301") (pin "4") (pinfunction "4_4") (pintype "passive"))
      (node (ref "MOD301") (pin "31") (pinfunction "P25_31") (pintype "passive"))
    )
    (net (code "76") (name "Net-(MOD301-P26)") (class "Default")
      (node (ref "J303") (pin "20") (pinfunction "20_20") (pintype "passive"))
      (node (ref "MOD301") (pin "14") (pinfunction "P26_14") (pintype "passive"))
    )
    (net (code "77") (name "Net-(MOD301-P30)") (class "Default")
      (node (ref "J303") (pin "16") (pinfunction "16_16") (pintype "passive"))
      (node (ref "MOD301") (pin "16") (pinfunction "P30_16") (pintype "passive"))
    )
    (net (code "78") (name "Net-(MOD301-P31)") (class "Default")
      (node (ref "J303") (pin "4") (pinfunction "4_4") (pintype "passive"))
      (node (ref "MOD301") (pin "22") (pinfunction "P31_22") (pintype "passive"))
    )
    (net (code "79") (name "Net-(MOD301-P32)") (class "Default")
      (node (ref "J301") (pin "12") (pinfunction "12_12") (pintype "passive"))
      (node (ref "MOD301") (pin "27") (pinfunction "P32_27") (pintype "passive"))
    )
    (net (code "80") (name "Net-(MOD301-P33)") (class "Default")
      (node (ref "J301") (pin "16") (pinfunction "16_16") (pintype "passive"))
      (node (ref "MOD301") (pin "25") (pinfunction "P33_25") (pintype "passive"))
    )
    (net (code "81") (name "Net-(MOD301-P34)") (class "Default")
      (node (ref "J303") (pin "6") (pinfunction "6_6") (pintype "passive"))
      (node (ref "MOD301") (pin "21") (pinfunction "P34_21") (pintype "passive"))
    )
    (net (code "82") (name "Net-(MOD301-P35)") (class "Default")
      (node (ref "J301") (pin "18") (pinfunction "18_18") (pintype "passive"))
      (node (ref "MOD301") (pin "24") (pinfunction "P35_24") (pintype "passive"))
    )
    (net (code "83") (name "Net-(MOD301-P36)") (class "Default")
      (node (ref "J301") (pin "10") (pinfunction "10_10") (pintype "passive"))
      (node (ref "MOD301") (pin "28") (pinfunction "P36_28") (pintype "passive"))
    )
    (net (code "84") (name "Net-(MOD301-P37)") (class "Default")
      (node (ref "J303") (pin "2") (pinfunction "2_2") (pintype "passive"))
      (node (ref "MOD301") (pin "23") (pinfunction "P37_23") (pintype "passive"))
    )
    (net (code "85") (name "Net-(MOD301-VAN)") (class "Default")
      (node (ref "J303") (pin "8") (pinfunction "8_8") (pintype "passive"))
      (node (ref "MOD301") (pin "20") (pinfunction "VAN_20") (pintype "power_in"))
    )
    (net (code "86") (name "Net-(MOD301-VDD)") (class "Default")
      (node (ref "J302") (pin "13") (pinfunction "13_13") (pintype "passive"))
      (node (ref "MOD301") (pin "7") (pinfunction "VDD_7") (pintype "power_in"))
    )
    (net (code "87") (name "Net-(MOD301-VDR)") (class "Default")
      (node (ref "J303") (pin "22") (pinfunction "22_22") (pintype "passive"))
      (node (ref "MOD301") (pin "13") (pinfunction "VDR_13") (pintype "power_in"))
    )
    (net (code "88") (name "Net-(MOD301-Vref)") (class "Default")
      (node (ref "J301") (pin "14") (pinfunction "14_14") (pintype "passive"))
      (node (ref "MOD301") (pin "26") (pinfunction "Vref_26") (pintype "power_in"))
    )
    (net (code "89") (name "Net-(MOD301-XRES)") (class "Default")
      (node (ref "J301") (pin "8") (pinfunction "8_8") (pintype "passive"))
      (node (ref "MOD301") (pin "29") (pinfunction "XRES_29") (pintype "passive"))
    )
    (net (code "90") (name "Net-(Q301-1)") (class "Default")
      (node (ref "Q301") (pin "G") (pinfunction "1_G") (pintype "passive"))
      (node (ref "R316") (pin "1") (pintype "passive"))
      (node (ref "R317") (pin "2") (pintype "passive"))
    )
    (net (code "91") (name "Net-(Q301-2)") (class "Default")
      (node (ref "Q301") (pin "S") (pinfunction "2_S") (pintype "passive"))
      (node (ref "R313") (pin "1") (pintype "passive"))
    )
    (net (code "92") (name "Net-(Q301-3)") (class "Default")
      (node (ref "Q301") (pin "D") (pinfunction "3_D") (pintype "passive"))
      (node (ref "R312") (pin "2") (pintype "passive"))
    )
    (net (code "93") (name "Net-(Q302-2)") (class "Default")
      (node (ref "Q302") (pin "S") (pinfunction "2_S") (pintype "passive"))
      (node (ref "R320") (pin "1") (pintype "passive"))
    )
    (net (code "94") (name "Net-(Q302-3)") (class "Default")
      (node (ref "Q302") (pin "D") (pinfunction "3_D") (pintype "passive"))
      (node (ref "R317") (pin "1") (pintype "passive"))
    )
    (net (code "95") (name "Net-(Q303-1)") (class "Default")
      (node (ref "Q303") (pin "G") (pinfunction "1_G") (pintype "passive"))
      (node (ref "R319") (pin "2") (pintype "passive"))
    )
    (net (code "96") (name "Net-(Q303-2)") (class "Default")
      (node (ref "Q303") (pin "S") (pinfunction "2_S") (pintype "passive"))
      (node (ref "R314") (pin "1") (pintype "passive"))
      (node (ref "R318") (pin "1") (pintype "passive"))
    )
    (net (code "97") (name "Net-(TP304-Test_Point)") (class "Default")
      (node (ref "J302") (pin "10") (pinfunction "10_10") (pintype "passive"))
      (node (ref "TP304") (pin "1") (pinfunction "Test_Point_1") (pintype "passive"))
    )
    (net (code "98") (name "Net-(TP305-Test_Point)") (class "Default")
      (node (ref "J301") (pin "13") (pinfunction "13_13") (pintype "passive"))
      (node (ref "TP305") (pin "1") (pinfunction "Test_Point_1") (pintype "passive"))
    )
    (net (code "99") (name "Net-(TP307-Test_Point)") (class "Default")
      (node (ref "D303") (pin "2") (pinfunction "2_2") (pintype "passive"))
      (node (ref "R310") (pin "1") (pintype "passive"))
      (node (ref "R312") (pin "1") (pintype "passive"))
      (node (ref "SW302") (pin "2") (pinfunction "COM_2") (pintype "passive"))
      (node (ref "TP307") (pin "1") (pinfunction "Test_Point_1") (pintype "passive"))
    )
    (net (code "100") (name "Net-(TP310-Test_Point)") (class "Default")
      (node (ref "C303") (pin "2") (pinfunction "2_2") (pintype "passive"))
      (node (ref "R315") (pin "2") (pintype "passive"))
      (node (ref "R316") (pin "2") (pintype "passive"))
      (node (ref "TP310") (pin "1") (pinfunction "Test_Point_1") (pintype "passive"))
    )
    (net (code "101") (name "Net-(TP314-Test_Point)") (class "Default")
      (node (ref "TP314") (pin "1") (pinfunction "Test_Point_1") (pintype "passive"))
      (node (ref "U301") (pin "2") (pinfunction "P1_2") (pintype "passive"))
    )
    (net (code "102") (name "Net-(TP315-Test_Point)") (class "Default")
      (node (ref "TP315") (pin "1") (pinfunction "Test_Point_1") (pintype "passive"))
      (node (ref "U301") (pin "3") (pinfunction "P2_3") (pintype "passive"))
    )
    (net (code "103") (name "Net-(TP316-Test_Point)") (class "Default")
      (node (ref "TP316") (pin "1") (pinfunction "Test_Point_1") (pintype "passive"))
      (node (ref "U301") (pin "4") (pinfunction "P3_4") (pintype "passive"))
    )
    (net (code "104") (name "Net-(TP317-Test_Point)") (class "Default")
      (node (ref "TP317") (pin "1") (pinfunction "Test_Point_1") (pintype "passive"))
      (node (ref "U301") (pin "6") (pinfunction "P4_6") (pintype "passive"))
    )
    (net (code "105") (name "Net-(TP320-Test_Point)") (class "Default")
      (node (ref "TP320") (pin "1") (pinfunction "Test_Point_1") (pintype "passive"))
      (node (ref "U301") (pin "8") (pinfunction "P6_8") (pintype "passive"))
    )
    (net (code "106") (name "Net-(U301-P0)") (class "Default")
      (node (ref "R321") (pin "1") (pintype "passive"))
      (node (ref "U301") (pin "1") (pinfunction "P0_1") (pintype "passive"))
    )
    (net (code "107") (name "Net-(U301-P7)") (class "Default")
      (node (ref "R336") (pin "1") (pintype "passive"))
      (node (ref "U301") (pin "9") (pinfunction "P7_9") (pintype "passive"))
    )
    (net (code "108") (name "Net-(U301-SCL)") (class "Default")
      (node (ref "R330") (pin "2") (pintype "passive"))
      (node (ref "U301") (pin "10") (pinfunction "SCL_10") (pintype "passive"))
    )
    (net (code "109") (name "Net-(U301-SDA)") (class "Default")
      (node (ref "R332") (pin "2") (pintype "passive"))
      (node (ref "U301") (pin "11") (pinfunction "SDA_11") (pintype "passive"))
    )
    (net (code "110") (name "Net-(U301-VDD)") (class "Default")
      (node (ref "R324") (pin "2") (pintype "passive"))
      (node (ref "TP312") (pin "2") (pintype "power_in"))
      (node (ref "U301") (pin "12") (pinfunction "VDD_12") (pintype "passive"))
    )
    (net (code "111") (name "Net-(U302-SCL)") (class "Default")
      (node (ref "R323") (pin "2") (pintype "passive"))
      (node (ref "U302") (pin "E1") (pinfunction "SCL_E1") (pintype "passive"))
    )
    (net (code "112") (name "Net-(U302-SDA)") (class "Default")
      (node (ref "R327") (pin "2") (pintype "passive"))
      (node (ref "U302") (pin "D2") (pinfunction "SDA_D2") (pintype "passive"))
    )
    (net (code "113") (name "Net-(U302-VCC)") (class "Default")
      (node (ref "R325") (pin "1") (pintype "passive"))
      (node (ref "TP313") (pin "1") (pintype "power_in"))
      (node (ref "U302") (pin "C1") (pinfunction "VCC_C1") (pintype "passive"))
    )
    (net (code "114") (name "VBATT") (class "Default")
      (node (ref "SW302") (pin "1") (pinfunction "1_1") (pintype "passive"))
    )
    (net (code "115") (name "unconnected-(J304-NC-Pad6)") (class "Default")
      (node (ref "J304") (pin "6") (pinfunction "NC_6") (pintype "passive+no_connect"))
    )
    (net (code "116") (name "unconnected-(SW302-COM-Pad5)") (class "Default")
      (node (ref "SW302") (pin "5") (pinfunction "COM_5") (pintype "passive+no_connect"))
    )
    (net (code "117") (name "unconnected-(SW302-Pad3)") (class "Default")
      (node (ref "SW302") (pin "3") (pinfunction "3_3") (pintype "passive+no_connect"))
    )
    (net (code "118") (name "unconnected-(SW302-Pad4)") (class "Default")
      (node (ref "SW302") (pin "4") (pinfunction "4_4") (pintype "passive+no_connect"))
    )
    (net (code "119") (name "unconnected-(SW302-Pad6)") (class "Default")
      (node (ref "SW302") (pin "6") (pinfunction "6_6") (pintype "passive+no_connect"))
    )
    (net (code "120") (name "unconnected-(U302-~{WC}-PadA1)") (class "Default")
      (node (ref "U302") (pin "A1") (pinfunction "~{WC}_A1") (pintype "passive+no_connect"))
    )
  )
)
